# Net_Names_1.net
KiCad netlist of a schematic drawn in Altium Designer
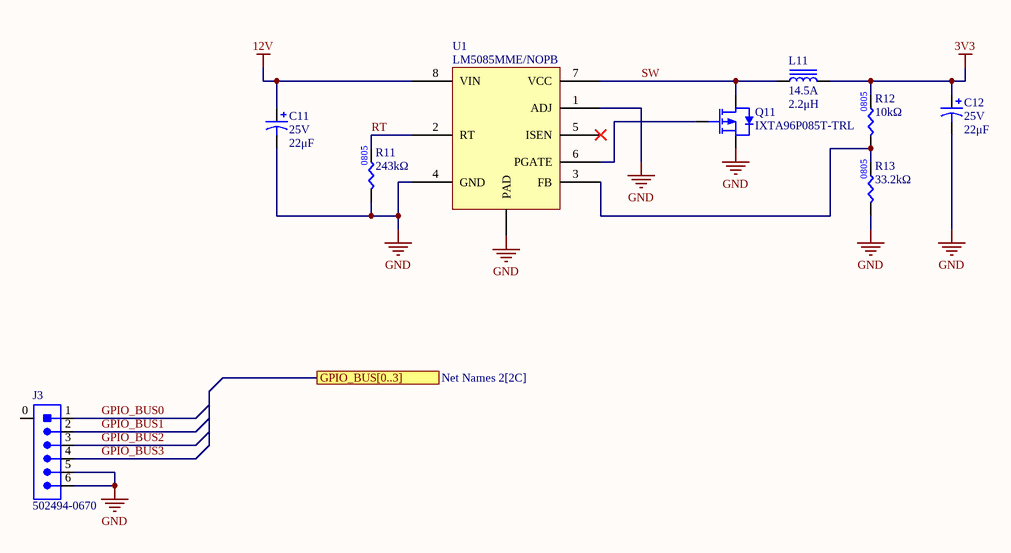
[diagram p0: Net Names 1.SchDoc]

(export (version "E")
  (design (tool "Eeschema 10.0.6"))
  (components
    (comp (ref "C11")
      (value "22μF")
      (footprint "CAP2917")
      (description "CAP TANT 22UF 20% 25V 2917")
      (fields (field (name "VOLTAGE RATING") "25V") (field (name "Comment") "CAP_22uF_25V_TANT"))
      (libsource (lib "UWRT_Schematic_Library_2020") (part "CAP_22uF_25V_TANT"))
    )
    (comp (ref "C12")
      (value "22μF")
      (footprint "CAP2917")
      (description "CAP TANT 22UF 20% 25V 2917")
      (fields (field (name "VOLTAGE RATING") "25V") (field (name "Comment") "CAP_22uF_25V_TANT"))
      (libsource (lib "UWRT_Schematic_Library_2020") (part "CAP_22uF_25V_TANT"))
    )
    (comp (ref "J3")
      (value "CON_6M_SM_RA")
      (footprint "MOLEX-5024940670")
      (description "CONN HEADER SMD RIGHT ANGLE 2MM PITCH")
      (fields (field (name "MANUFACTURER PART NUMBER 1") "502494-0670"))
      (libsource (lib "UWRT_Schematic_Library_2020") (part "CON_6M_SM_RA"))
    )
    (comp (ref "L11")
      (value "IND_2.2uH_14.5A")
      (footprint "IND_VISHAY_IHLP3232DZER2R2M11")
      (description "INDUCTOR 2.2UH 14.5A 9.41 MOHM")
      (fields (field (name "CURRENT RATING") "14.5A") (field (name "INDUCTANCE") "2.2μH"))
      (libsource (lib "UWRT_Schematic_Library_2020") (part "IND_2.2uH_14.5A"))
    )
    (comp (ref "Q11")
      (value "PMOS_85V_96A")
      (footprint "D-PAK")
      (description "MOSFET P-CH 85V 96A TO263")
      (fields (field (name "MANUFACTURER PART NUMBER 1") "IXTA96P085T-TRL"))
      (libsource (lib "UWRT_Schematic_Library_2020") (part "PMOS_85V_96A"))
    )
    (comp (ref "R11")
      (value "243kΩ")
      (footprint "RES0805")
      (description "RES 243K OHM 1% 1/8W 0805")
      (fields (field (name "Comment") "RES_243kΩ_0805_1%"))
      (libsource (lib "UWRT_Schematic_Library_2020") (part "RES_243kΩ_0805_1%"))
    )
    (comp (ref "R12")
      (value "10kΩ")
      (footprint "RES0805")
      (description "RES 10K OHM 5% 1/8W 0805")
      (fields (field (name "LCSC PART #") "C17414") (field (name "Comment") "RES_10kΩ_0805_5%"))
      (libsource (lib "UWRT_Schematic_Library_2020") (part "RES_10kΩ_0805_5%"))
    )
    (comp (ref "R13")
      (value "33.2kΩ")
      (footprint "RES0805")
      (description "RES 33.2K OHM 1% 1/8W 0805")
      (fields (field (name "Comment") "RES_33.2kΩ_0805_1%"))
      (libsource (lib "UWRT_Schematic_Library_2020") (part "RES_33.2kΩ_0805_1%"))
    )
    (comp (ref "U1")
      (value "BUCK_LMR14050SDDAR")
      (footprint "8-VSSOP")
      (description "IC REG CTRLR BUCK 8VSSOP")
      (fields (field (name "MANUFACTURER PART NUMBER 1") "LM5085MME/NOPB"))
      (libsource (lib "UWRT_Schematic_Library_2020") (part "BUCK_LM5085"))
    )
  )
  (nets
    (net (code "1") (name "/GPIO_BUS0") (class "Default")
      (node (ref "J3") (pin "1") (pinfunction "1_1") (pintype "passive"))
    )
    (net (code "2") (name "/GPIO_BUS1") (class "Default")
      (node (ref "J3") (pin "2") (pinfunction "2_2") (pintype "passive"))
    )
    (net (code "3") (name "/GPIO_BUS2") (class "Default")
      (node (ref "J3") (pin "3") (pinfunction "3_3") (pintype "passive"))
    )
    (net (code "4") (name "/GPIO_BUS3") (class "Default")
      (node (ref "J3") (pin "4") (pinfunction "4_4") (pintype "passive"))
    )
    (net (code "6") (name "/RT") (class "Default")
      (node (ref "R11") (pin "2") (pinfunction "2_2") (pintype "passive"))
      (node (ref "U1") (pin "2") (pinfunction "RT_2") (pintype "passive"))
    )
    (net (code "7") (name "/SW") (class "Default")
      (node (ref "L11") (pin "1") (pinfunction "1_1") (pintype "passive"))
      (node (ref "Q11") (pin "1") (pinfunction "Drain_1") (pintype "passive"))
      (node (ref "U1") (pin "7") (pinfunction "VCC_7") (pintype "passive"))
    )
    (net (code "8") (name "3V3") (class "Default")
      (node (ref "C12") (pin "1") (pinfunction "1_1") (pintype "passive"))
      (node (ref "L11") (pin "2") (pinfunction "2_2") (pintype "passive"))
      (node (ref "R12") (pin "2") (pinfunction "2_2") (pintype "passive"))
    )
    (net (code "9") (name "12V") (class "Default")
      (node (ref "C11") (pin "1") (pinfunction "1_1") (pintype "passive"))
      (node (ref "U1") (pin "8") (pinfunction "VIN_8") (pintype "passive"))
    )
    (net (code "10") (name "GND") (class "Default")
      (node (ref "C11") (pin "2") (pinfunction "2_2") (pintype "passive"))
      (node (ref "C12") (pin "2") (pinfunction "2_2") (pintype "passive"))
      (node (ref "J3") (pin "5") (pinfunction "5_5") (pintype "passive"))
      (node (ref "J3") (pin "6") (pinfunction "6_6") (pintype "passive"))
      (node (ref "Q11") (pin "3") (pinfunction "Source_3") (pintype "passive"))
      (node (ref "R11") (pin "1") (pinfunction "1_1") (pintype "passive"))
      (node (ref "R13") (pin "1") (pinfunction "1_1") (pintype "passive"))
      (node (ref "U1") (pin "1") (pinfunction "ADJ_1") (pintype "passive"))
      (node (ref "U1") (pin "4") (pinfunction "GND_4") (pintype "passive"))
      (node (ref "U1") (pin "9") (pinfunction "PAD_9") (pintype "passive"))
    )
    (net (code "11") (name "Net-(Q11-Gate)") (class "Default")
      (node (ref "Q11") (pin "2") (pinfunction "Gate_2") (pintype "passive"))
      (node (ref "U1") (pin "6") (pinfunction "PGATE_6") (pintype "passive"))
    )
    (net (code "12") (name "Net-(U1-FB)") (class "Default")
      (node (ref "R12") (pin "1") (pinfunction "1_1") (pintype "passive"))
      (node (ref "R13") (pin "2") (pinfunction "2_2") (pintype "passive"))
      (node (ref "U1") (pin "3") (pinfunction "FB_3") (pintype "passive"))
    )
    (net (code "13") (name "unconnected-(J3-Pad0)") (class "Default")
      (node (ref "J3") (pin "0") (pinfunction "0_0") (pintype "passive"))
    )
    (net (code "14") (name "unconnected-(U1-ISEN-Pad5)") (class "Default")
      (node (ref "U1") (pin "5") (pinfunction "ISEN_5") (pintype "passive+no_connect"))
    )
  )
)
